# Board.net
KiCad netlist of a schematic drawn in EAGLE
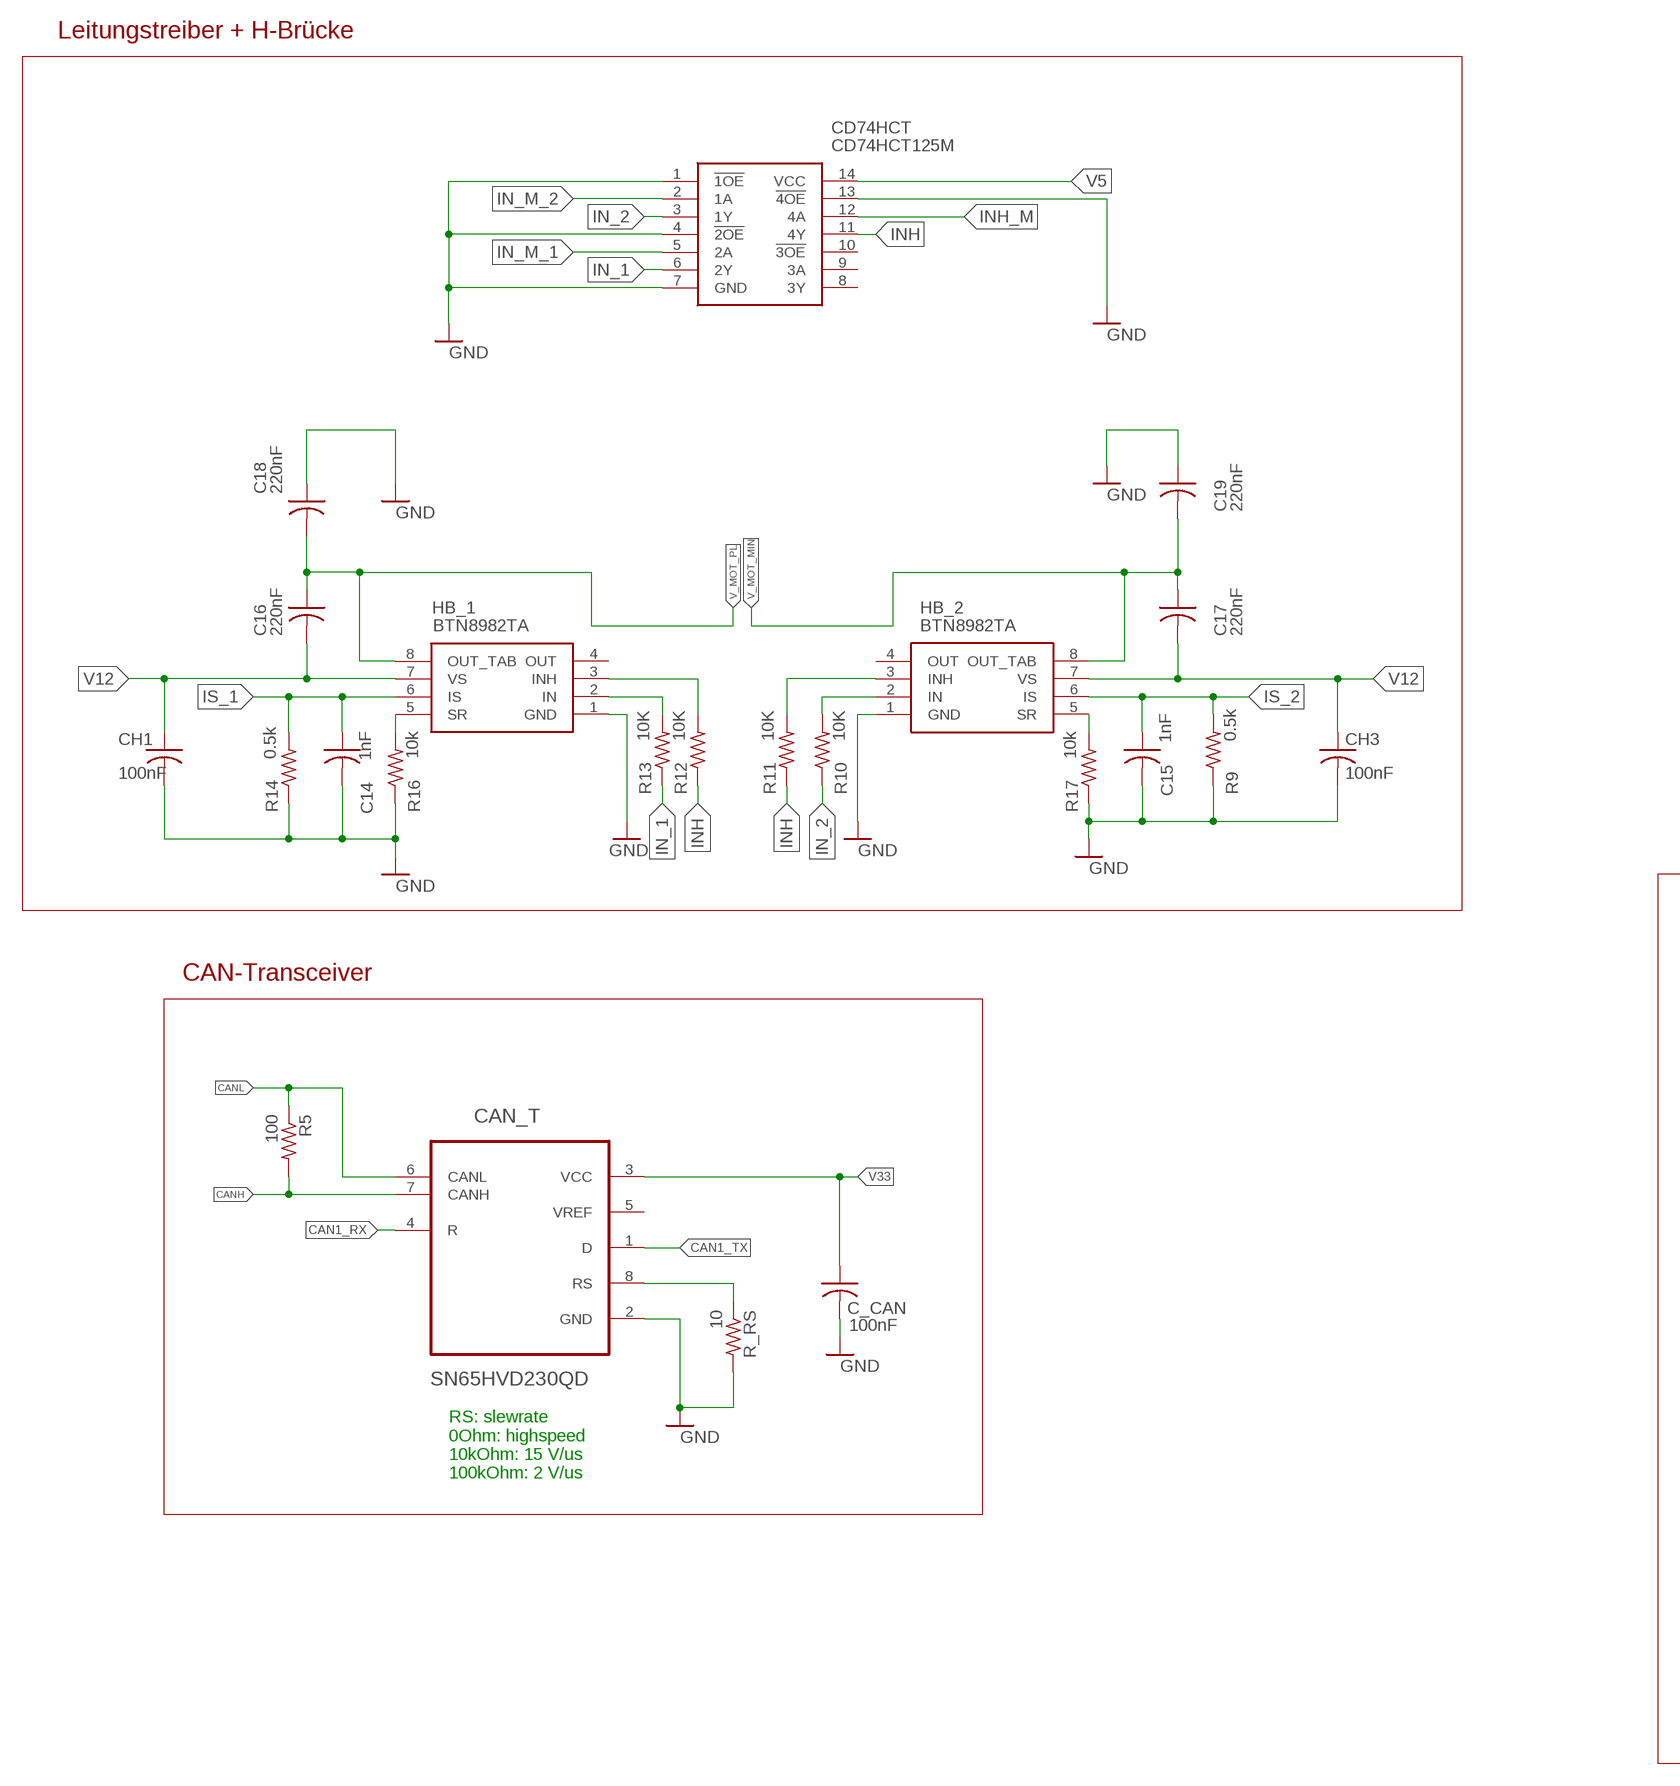
[diagram p0: schematic, sheet 1, part 1 of 2]
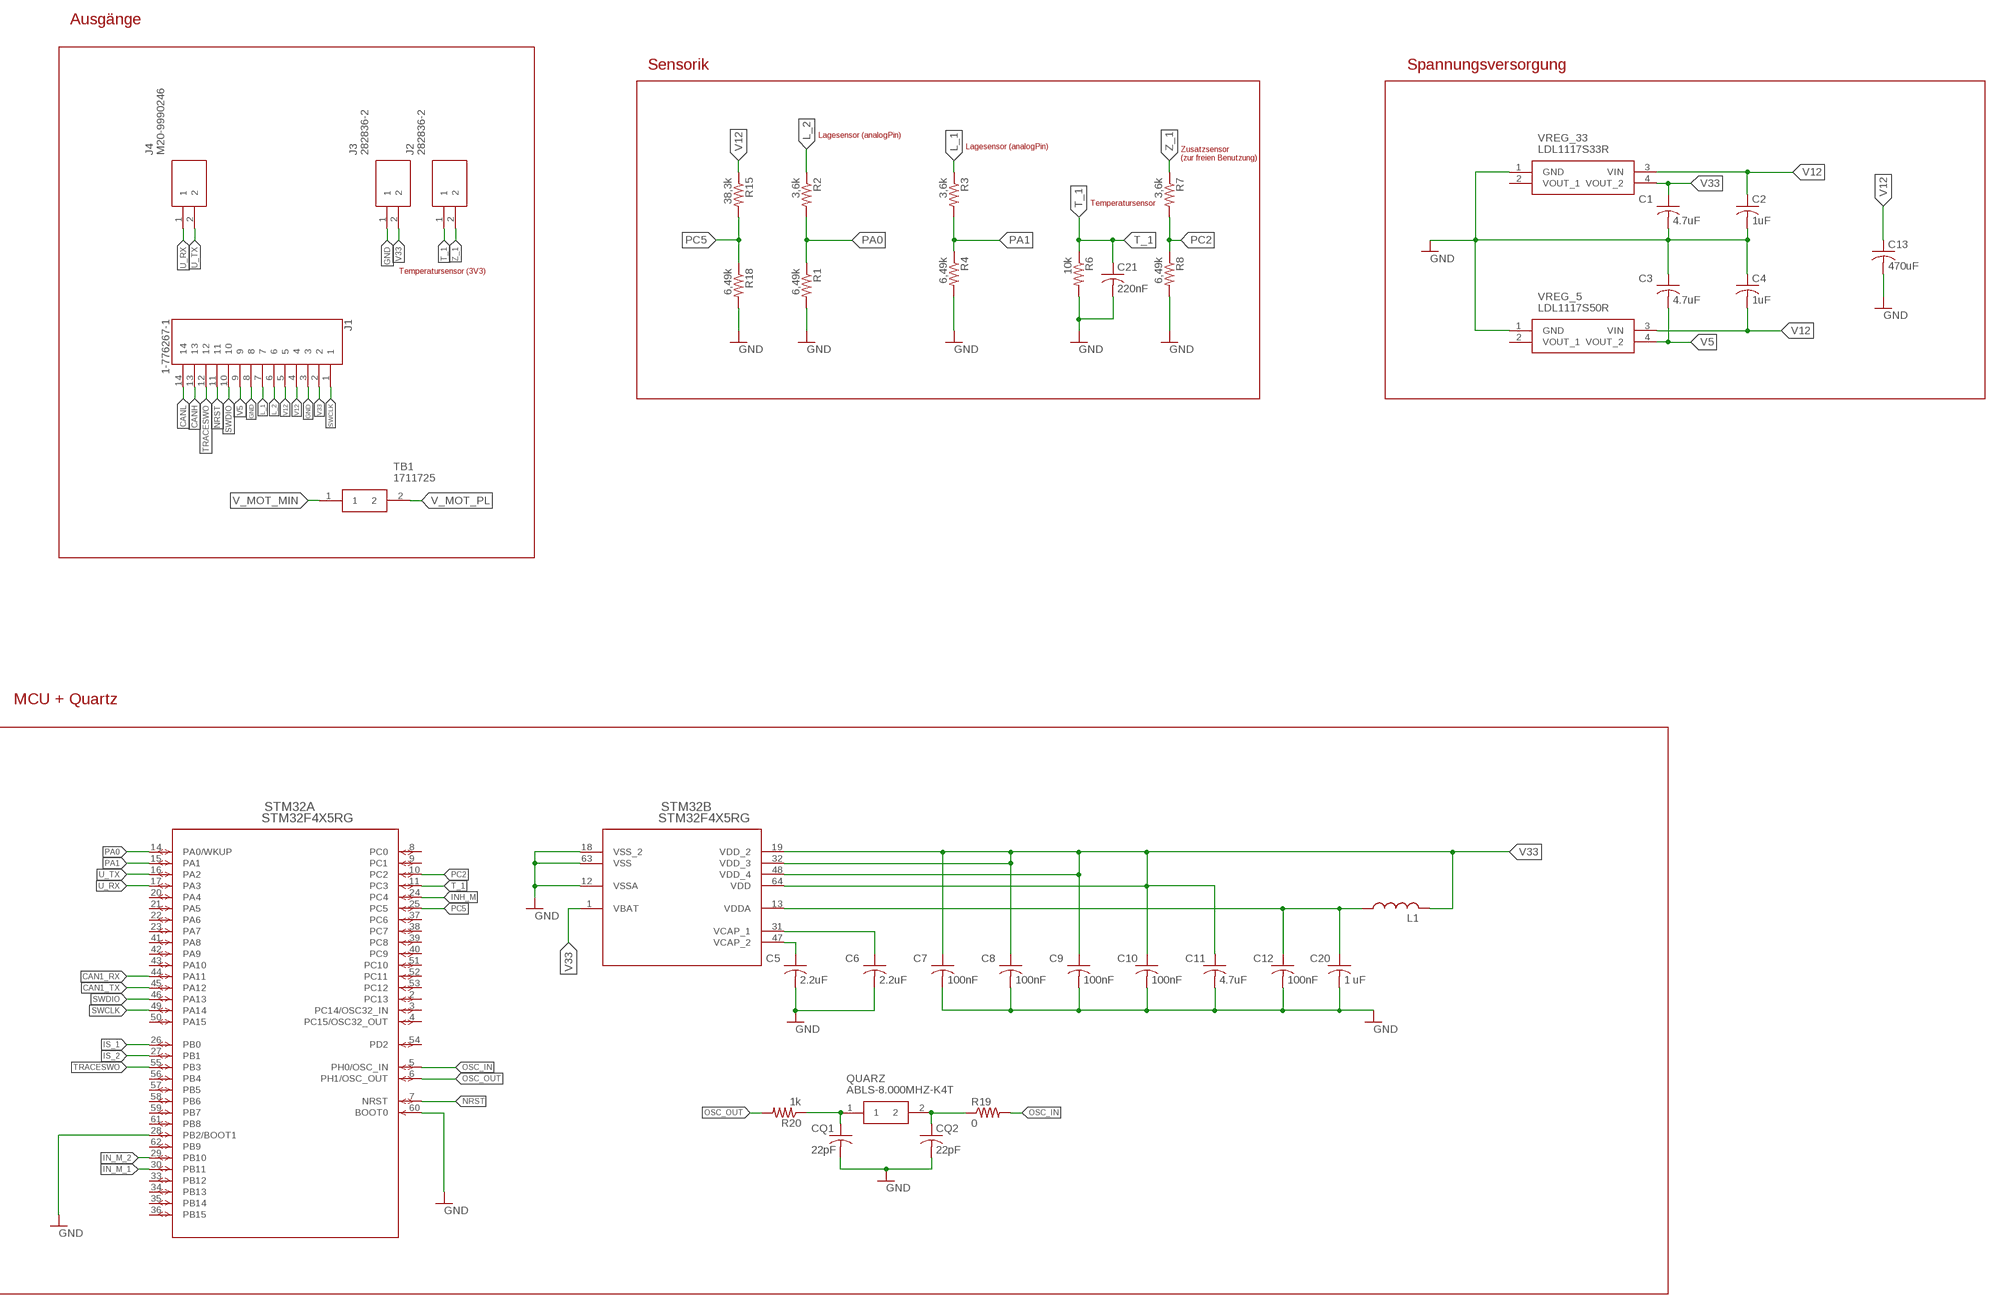
[diagram p1: schematic, sheet 1, part 2 of 2]

(export (version "E")
  (design (tool "Eeschema 10.0.6"))
  (components
    (comp (ref "C1")
      (value "4.7uF")
      (footprint "eagle-import:C1206")
      (libsource (lib "eagle-import") (part "C-USC1206"))
    )
    (comp (ref "C2")
      (value "1uF")
      (footprint "eagle-import:C1206")
      (libsource (lib "eagle-import") (part "C-USC1206"))
    )
    (comp (ref "C3")
      (value "4.7uF")
      (footprint "eagle-import:C1206")
      (libsource (lib "eagle-import") (part "C-USC1206"))
    )
    (comp (ref "C4")
      (value "1uF")
      (footprint "eagle-import:C1206")
      (libsource (lib "eagle-import") (part "C-USC1206"))
    )
    (comp (ref "C5")
      (value "2.2uF")
      (footprint "eagle-import:C1206")
      (libsource (lib "eagle-import") (part "C-USC1206"))
    )
    (comp (ref "C6")
      (value "2.2uF")
      (footprint "eagle-import:C1206")
      (libsource (lib "eagle-import") (part "C-USC1206"))
    )
    (comp (ref "C7")
      (value "100nF")
      (footprint "eagle-import:C1206")
      (libsource (lib "eagle-import") (part "C-USC1206"))
    )
    (comp (ref "C8")
      (value "100nF")
      (footprint "eagle-import:C1206")
      (libsource (lib "eagle-import") (part "C-USC1206"))
    )
    (comp (ref "C9")
      (value "100nF")
      (footprint "eagle-import:C1206")
      (libsource (lib "eagle-import") (part "C-USC1206"))
    )
    (comp (ref "C10")
      (value "100nF")
      (footprint "eagle-import:C1206")
      (libsource (lib "eagle-import") (part "C-USC1206"))
    )
    (comp (ref "C11")
      (value "4.7uF")
      (footprint "eagle-import:C1206")
      (libsource (lib "eagle-import") (part "C-USC1206"))
    )
    (comp (ref "C12")
      (value "100nF")
      (footprint "eagle-import:C1206")
      (libsource (lib "eagle-import") (part "C-USC1206"))
    )
    (comp (ref "C13")
      (value "470uF")
      (footprint "eagle-import:C050-075X075")
      (libsource (lib "eagle-import") (part "C-US050-075X075"))
    )
    (comp (ref "C14")
      (value "1nF")
      (footprint "eagle-import:C1206")
      (libsource (lib "eagle-import") (part "C-USC1206"))
    )
    (comp (ref "C15")
      (value "1nF")
      (footprint "eagle-import:C1206")
      (libsource (lib "eagle-import") (part "C-USC1206"))
    )
    (comp (ref "C16")
      (value "220nF")
      (footprint "eagle-import:C1206")
      (libsource (lib "eagle-import") (part "C-USC1206"))
    )
    (comp (ref "C17")
      (value "220nF")
      (footprint "eagle-import:C1206")
      (libsource (lib "eagle-import") (part "C-USC1206"))
    )
    (comp (ref "C18")
      (value "220nF")
      (footprint "eagle-import:C1206")
      (libsource (lib "eagle-import") (part "C-USC1206"))
    )
    (comp (ref "C19")
      (value "220nF")
      (footprint "eagle-import:C1206")
      (libsource (lib "eagle-import") (part "C-USC1206"))
    )
    (comp (ref "C20")
      (value "1 uF")
      (footprint "eagle-import:C1206")
      (libsource (lib "eagle-import") (part "C-USC1206"))
    )
    (comp (ref "C21")
      (value "220nF")
      (footprint "eagle-import:C1206")
      (libsource (lib "eagle-import") (part "C-USC1206"))
    )
    (comp (ref "CAN_T")
      (value "SN65HVD230QD")
      (footprint "eagle-import:SOIC127P600X175-8N")
      (fields (field (name "MF") "TEXAS INSTRUMENTS") (field (name "MPN") "SN65HVD230QD.."))
      (libsource (lib "eagle-import") (part "SN65HVD230QD"))
    )
    (comp (ref "CD74HCT")
      (value "CD74HCT125M")
      (footprint "eagle-import:SOIC127P600X175-14N")
      (fields (field (name "MOUSER_PART_NUMBER") "595-CD74HCT125M"))
      (libsource (lib "eagle-import") (part "CD74HCT125M"))
    )
    (comp (ref "CH1")
      (value "100nF")
      (footprint "eagle-import:C1206")
      (libsource (lib "eagle-import") (part "C-USC1206"))
    )
    (comp (ref "CH3")
      (value "100nF")
      (footprint "eagle-import:C1206")
      (libsource (lib "eagle-import") (part "C-USC1206"))
    )
    (comp (ref "CQ1")
      (value "22pF")
      (footprint "eagle-import:C0805")
      (libsource (lib "eagle-import") (part "C-USC0805"))
    )
    (comp (ref "CQ2")
      (value "22pF")
      (footprint "eagle-import:C0805")
      (libsource (lib "eagle-import") (part "C-USC0805"))
    )
    (comp (ref "C_CAN")
      (value "100nF")
      (footprint "eagle-import:C1206")
      (libsource (lib "eagle-import") (part "C-USC1206"))
    )
    (comp (ref "HB_1")
      (value "BTN8982TA")
      (footprint "eagle-import:TO127P1500X440-8N")
      (fields (field (name "MOUSER_PART_NUMBER") "726-BTN8982TA"))
      (libsource (lib "eagle-import") (part "BTN8982TA"))
    )
    (comp (ref "HB_2")
      (value "BTN8982TA")
      (footprint "eagle-import:TO127P1500X440-8N")
      (fields (field (name "MOUSER_PART_NUMBER") "726-BTN8982TA"))
      (libsource (lib "eagle-import") (part "BTN8982TA"))
    )
    (comp (ref "J1")
      (value "1-776267-1")
      (footprint "eagle-import:TE_1-776267-1")
      (fields (field (name "DIGI-KEY_PART_NUMBER") "A142413-ND") (field (name "MF") "TE Connectivity"))
      (libsource (lib "eagle-import") (part "1-776267-1"))
    )
    (comp (ref "J2")
      (value "282836-2")
      (footprint "eagle-import:SHDR2W100P0X500_1X2_1000X820X1")
      (fields (field (name "MOUSER_PART_NUMBER") "571-2828362"))
      (libsource (lib "eagle-import") (part "282836-2"))
    )
    (comp (ref "J3")
      (value "282836-2")
      (footprint "eagle-import:SHDR2W100P0X500_1X2_1000X820X1")
      (fields (field (name "MOUSER_PART_NUMBER") "571-2828362"))
      (libsource (lib "eagle-import") (part "282836-2"))
    )
    (comp (ref "J4")
      (value "M20-9990246")
      (footprint "eagle-import:HDRV2W64P0X254_1X2_508X254X864")
      (fields (field (name "MOUSER_PART_NUMBER") "855-M20-9990246"))
      (libsource (lib "eagle-import") (part "M20-9990246"))
    )
    (comp (ref "L1")
      (value "INDUCTOR_0805_N")
      (footprint "eagle-import:RESC0805_N")
      (libsource (lib "eagle-import") (part "INDUCTOR_0805_N"))
    )
    (comp (ref "QUARZ")
      (value "ABLS-8.000MHZ-K4T")
      (footprint "eagle-import:ABLS-12.000MHZ-B2")
      (fields (field (name "MOUSER_PART_NUMBER") "815-ABLS-8.0MK4-T") (field (name "MF") "ABRACON"))
      (libsource (lib "eagle-import") (part "ABLS-8.000MHZ-K4T"))
    )
    (comp (ref "R1")
      (value "6,49k")
      (footprint "eagle-import:R1206")
      (libsource (lib "eagle-import") (part "R-US_R1206"))
    )
    (comp (ref "R2")
      (value "3,6k")
      (footprint "eagle-import:R1206")
      (libsource (lib "eagle-import") (part "R-US_R1206"))
    )
    (comp (ref "R3")
      (value "3,6k")
      (footprint "eagle-import:R1206")
      (libsource (lib "eagle-import") (part "R-US_R1206"))
    )
    (comp (ref "R4")
      (value "6,49k")
      (footprint "eagle-import:R1206")
      (libsource (lib "eagle-import") (part "R-US_R1206"))
    )
    (comp (ref "R5")
      (value "100")
      (footprint "eagle-import:R1206")
      (libsource (lib "eagle-import") (part "R-US_R1206"))
    )
    (comp (ref "R6")
      (value "10k")
      (footprint "eagle-import:R1206")
      (libsource (lib "eagle-import") (part "R-US_R1206"))
    )
    (comp (ref "R7")
      (value "3,6k")
      (footprint "eagle-import:R1206")
      (libsource (lib "eagle-import") (part "R-US_R1206"))
    )
    (comp (ref "R8")
      (value "6,49k")
      (footprint "eagle-import:R1206")
      (libsource (lib "eagle-import") (part "R-US_R1206"))
    )
    (comp (ref "R9")
      (value "0.5k")
      (footprint "eagle-import:R1206")
      (libsource (lib "eagle-import") (part "R-US_R1206"))
    )
    (comp (ref "R10")
      (value "10K")
      (footprint "eagle-import:R1206")
      (libsource (lib "eagle-import") (part "R-US_R1206"))
    )
    (comp (ref "R11")
      (value "10K")
      (footprint "eagle-import:R1206")
      (libsource (lib "eagle-import") (part "R-US_R1206"))
    )
    (comp (ref "R12")
      (value "10K")
      (footprint "eagle-import:R1206")
      (libsource (lib "eagle-import") (part "R-US_R1206"))
    )
    (comp (ref "R13")
      (value "10K")
      (footprint "eagle-import:R1206")
      (libsource (lib "eagle-import") (part "R-US_R1206"))
    )
    (comp (ref "R14")
      (value "0.5k")
      (footprint "eagle-import:R1206")
      (libsource (lib "eagle-import") (part "R-US_R1206"))
    )
    (comp (ref "R15")
      (value "38,3k")
      (footprint "eagle-import:R1206")
      (libsource (lib "eagle-import") (part "R-US_R1206"))
    )
    (comp (ref "R16")
      (value "10k")
      (footprint "eagle-import:R0805")
      (libsource (lib "eagle-import") (part "resistor_348_R-US_R0805"))
    )
    (comp (ref "R17")
      (value "10k")
      (footprint "eagle-import:R0805")
      (libsource (lib "eagle-import") (part "resistor_348_R-US_R0805"))
    )
    (comp (ref "R18")
      (value "6,49k")
      (footprint "eagle-import:R1206")
      (libsource (lib "eagle-import") (part "R-US_R1206"))
    )
    (comp (ref "R19")
      (value "0")
      (footprint "eagle-import:R0805")
      (libsource (lib "eagle-import") (part "resistor_348_R-US_R0805"))
    )
    (comp (ref "R20")
      (value "1k")
      (footprint "eagle-import:R0805")
      (libsource (lib "eagle-import") (part "resistor_348_R-US_R0805"))
    )
    (comp (ref "R_RS")
      (value "10")
      (footprint "eagle-import:R1206")
      (libsource (lib "eagle-import") (part "R-US_R1206"))
    )
    (comp (ref "STM32")
      (value "STM32F4X5RG")
      (footprint "eagle-import:LQFP64-10X10MM")
      (fields (field (name "OC_FARNELL") "unknown"))
      (libsource (lib "eagle-import") (part "STM32F4X5RG"))
    )
    (comp (ref "TB1")
      (value "1711725")
      (footprint "eagle-import:PHEONIX-5.08PITCH-2PIN")
      (fields (field (name "MOUSER_PART_NUMBER") "651-1711725"))
      (libsource (lib "eagle-import") (part "1711725"))
    )
    (comp (ref "VREG_5")
      (value "LDL1117S50R")
      (footprint "eagle-import:SOT230P700X180-4N")
      (fields (field (name "MOUSER_PART_NUMBER") "511-LDL1117S50R") (field (name "MF") "STMICROELECTRONICS"))
      (libsource (lib "eagle-import") (part "LDL1117S50R"))
    )
    (comp (ref "VREG_33")
      (value "LDL1117S33R")
      (footprint "eagle-import:SOT230P700X180-4N")
      (fields (field (name "MOUSER_PART_NUMBER") "511-LDL1117S33R") (field (name "MF") "STMICROELECTRONICS"))
      (libsource (lib "eagle-import") (part "LDL1117S33R"))
    )
  )
  (nets
    (net (code "1") (name "CAN1_RX") (class "Default")
      (node (ref "CAN_T") (pin "4") (pinfunction "R_4") (pintype "output"))
      (node (ref "STM32") (pin "44") (pinfunction "PA11_44") (pintype "bidirectional"))
    )
    (net (code "2") (name "CAN1_TX") (class "Default")
      (node (ref "CAN_T") (pin "1") (pinfunction "D_1") (pintype "input"))
      (node (ref "STM32") (pin "45") (pinfunction "PA12_45") (pintype "bidirectional"))
    )
    (net (code "3") (name "CANH") (class "Default")
      (node (ref "CAN_T") (pin "7") (pinfunction "CANH_7") (pintype "output"))
      (node (ref "J1") (pin "13") (pinfunction "13_13") (pintype "passive"))
      (node (ref "R5") (pin "2") (pinfunction "2_2") (pintype "passive"))
    )
    (net (code "4") (name "CANL") (class "Default")
      (node (ref "CAN_T") (pin "6") (pinfunction "CANL_6") (pintype "output"))
      (node (ref "J1") (pin "14") (pinfunction "14_14") (pintype "passive"))
      (node (ref "R5") (pin "1") (pinfunction "1_1") (pintype "passive"))
    )
    (net (code "5") (name "GND") (class "Default")
      (node (ref "C1") (pin "2") (pinfunction "2_2") (pintype "passive"))
      (node (ref "C10") (pin "2") (pinfunction "2_2") (pintype "passive"))
      (node (ref "C11") (pin "2") (pinfunction "2_2") (pintype "passive"))
      (node (ref "C12") (pin "2") (pinfunction "2_2") (pintype "passive"))
      (node (ref "C13") (pin "2") (pinfunction "2_2") (pintype "passive"))
      (node (ref "C14") (pin "2") (pinfunction "2_2") (pintype "passive"))
      (node (ref "C15") (pin "2") (pinfunction "2_2") (pintype "passive"))
      (node (ref "C18") (pin "1") (pinfunction "1_1") (pintype "passive"))
      (node (ref "C19") (pin "1") (pinfunction "1_1") (pintype "passive"))
      (node (ref "C2") (pin "2") (pinfunction "2_2") (pintype "passive"))
      (node (ref "C20") (pin "2") (pinfunction "2_2") (pintype "passive"))
      (node (ref "C21") (pin "2") (pinfunction "2_2") (pintype "passive"))
      (node (ref "C3") (pin "1") (pinfunction "1_1") (pintype "passive"))
      (node (ref "C4") (pin "1") (pinfunction "1_1") (pintype "passive"))
      (node (ref "C5") (pin "2") (pinfunction "2_2") (pintype "passive"))
      (node (ref "C6") (pin "2") (pinfunction "2_2") (pintype "passive"))
      (node (ref "C7") (pin "2") (pinfunction "2_2") (pintype "passive"))
      (node (ref "C8") (pin "2") (pinfunction "2_2") (pintype "passive"))
      (node (ref "C9") (pin "2") (pinfunction "2_2") (pintype "passive"))
      (node (ref "CAN_T") (pin "2") (pinfunction "GND_2") (pintype "passive"))
      (node (ref "CD74HCT") (pin "1") (pinfunction "~{1OE}_1") (pintype "bidirectional"))
      (node (ref "CD74HCT") (pin "13") (pinfunction "~{4OE}_13") (pintype "bidirectional"))
      (node (ref "CD74HCT") (pin "4") (pinfunction "~{2OE}_4") (pintype "bidirectional"))
      (node (ref "CD74HCT") (pin "7") (pinfunction "GND_7") (pintype "power_in"))
      (node (ref "CH1") (pin "2") (pinfunction "2_2") (pintype "passive"))
      (node (ref "CH3") (pin "2") (pinfunction "2_2") (pintype "passive"))
      (node (ref "CQ1") (pin "2") (pinfunction "2_2") (pintype "passive"))
      (node (ref "CQ2") (pin "2") (pinfunction "2_2") (pintype "passive"))
      (node (ref "C_CAN") (pin "2") (pinfunction "2_2") (pintype "passive"))
      (node (ref "HB_1") (pin "1") (pinfunction "GND_1") (pintype "power_in"))
      (node (ref "HB_2") (pin "1") (pinfunction "GND_1") (pintype "power_in"))
      (node (ref "J1") (pin "3") (pinfunction "3_3") (pintype "passive"))
      (node (ref "J1") (pin "8") (pinfunction "8_8") (pintype "passive"))
      (node (ref "J3") (pin "1") (pinfunction "1_1") (pintype "bidirectional"))
      (node (ref "R1") (pin "2") (pinfunction "2_2") (pintype "passive"))
      (node (ref "R14") (pin "1") (pinfunction "1_1") (pintype "passive"))
      (node (ref "R16") (pin "1") (pinfunction "1_1") (pintype "passive"))
      (node (ref "R17") (pin "1") (pinfunction "1_1") (pintype "passive"))
      (node (ref "R18") (pin "2") (pinfunction "2_2") (pintype "passive"))
      (node (ref "R4") (pin "2") (pinfunction "2_2") (pintype "passive"))
      (node (ref "R6") (pin "2") (pinfunction "2_2") (pintype "passive"))
      (node (ref "R8") (pin "2") (pinfunction "2_2") (pintype "passive"))
      (node (ref "R9") (pin "1") (pinfunction "1_1") (pintype "passive"))
      (node (ref "R_RS") (pin "2") (pinfunction "2_2") (pintype "passive"))
      (node (ref "STM32") (pin "12") (pinfunction "VSSA_12") (pintype "power_in"))
      (node (ref "STM32") (pin "18") (pinfunction "VSS_2_18") (pintype "power_in"))
      (node (ref "STM32") (pin "28") (pinfunction "PB2/BOOT1_28") (pintype "bidirectional"))
      (node (ref "STM32") (pin "60") (pinfunction "BOOT0_60") (pintype "input"))
      (node (ref "STM32") (pin "63") (pinfunction "VSS_63") (pintype "power_in"))
      (node (ref "VREG_33") (pin "1") (pinfunction "GND_1") (pintype "power_in"))
      (node (ref "VREG_5") (pin "1") (pinfunction "GND_1") (pintype "bidirectional"))
    )
    (net (code "6") (name "INH") (class "Default")
      (node (ref "CD74HCT") (pin "11") (pinfunction "4Y_11") (pintype "bidirectional"))
      (node (ref "R11") (pin "1") (pinfunction "1_1") (pintype "passive"))
      (node (ref "R12") (pin "1") (pinfunction "1_1") (pintype "passive"))
    )
    (net (code "7") (name "INH_M") (class "Default")
      (node (ref "CD74HCT") (pin "12") (pinfunction "4A_12") (pintype "bidirectional"))
      (node (ref "STM32") (pin "24") (pinfunction "PC4_24") (pintype "bidirectional"))
    )
    (net (code "8") (name "IN_1") (class "Default")
      (node (ref "CD74HCT") (pin "6") (pinfunction "2Y_6") (pintype "bidirectional"))
      (node (ref "R13") (pin "1") (pinfunction "1_1") (pintype "passive"))
    )
    (net (code "9") (name "IN_2") (class "Default")
      (node (ref "CD74HCT") (pin "3") (pinfunction "1Y_3") (pintype "bidirectional"))
      (node (ref "R10") (pin "1") (pinfunction "1_1") (pintype "passive"))
    )
    (net (code "10") (name "IN_M_1") (class "Default")
      (node (ref "CD74HCT") (pin "5") (pinfunction "2A_5") (pintype "bidirectional"))
      (node (ref "STM32") (pin "30") (pinfunction "PB11_30") (pintype "bidirectional"))
    )
    (net (code "11") (name "IN_M_2") (class "Default")
      (node (ref "CD74HCT") (pin "2") (pinfunction "1A_2") (pintype "bidirectional"))
      (node (ref "STM32") (pin "29") (pinfunction "PB10_29") (pintype "bidirectional"))
    )
    (net (code "12") (name "IS_1") (class "Default")
      (node (ref "C14") (pin "1") (pinfunction "1_1") (pintype "passive"))
      (node (ref "HB_1") (pin "6") (pinfunction "IS_6") (pintype "bidirectional"))
      (node (ref "R14") (pin "2") (pinfunction "2_2") (pintype "passive"))
      (node (ref "STM32") (pin "26") (pinfunction "PB0_26") (pintype "bidirectional"))
    )
    (net (code "13") (name "IS_2") (class "Default")
      (node (ref "C15") (pin "1") (pinfunction "1_1") (pintype "passive"))
      (node (ref "HB_2") (pin "6") (pinfunction "IS_6") (pintype "bidirectional"))
      (node (ref "R9") (pin "2") (pinfunction "2_2") (pintype "passive"))
      (node (ref "STM32") (pin "27") (pinfunction "PB1_27") (pintype "bidirectional"))
    )
    (net (code "14") (name "L_1") (class "Default")
      (node (ref "J1") (pin "7") (pinfunction "7_7") (pintype "passive"))
      (node (ref "R3") (pin "1") (pinfunction "1_1") (pintype "passive"))
    )
    (net (code "15") (name "L_2") (class "Default")
      (node (ref "J1") (pin "6") (pinfunction "6_6") (pintype "passive"))
      (node (ref "R2") (pin "1") (pinfunction "1_1") (pintype "passive"))
    )
    (net (code "16") (name "NRST") (class "Default")
      (node (ref "J1") (pin "11") (pinfunction "11_11") (pintype "passive"))
      (node (ref "STM32") (pin "7") (pinfunction "NRST_7") (pintype "bidirectional"))
    )
    (net (code "17") (name "Net-(CAN_T-RS)") (class "Default")
      (node (ref "CAN_T") (pin "8") (pinfunction "RS_8") (pintype "input"))
      (node (ref "R_RS") (pin "1") (pinfunction "1_1") (pintype "passive"))
    )
    (net (code "18") (name "Net-(CQ1-Pad1)") (class "Default")
      (node (ref "CQ1") (pin "1") (pinfunction "1_1") (pintype "passive"))
      (node (ref "QUARZ") (pin "1") (pinfunction "1_1") (pintype "bidirectional"))
      (node (ref "R20") (pin "1") (pinfunction "1_1") (pintype "passive"))
    )
    (net (code "19") (name "Net-(CQ2-Pad1)") (class "Default")
      (node (ref "CQ2") (pin "1") (pinfunction "1_1") (pintype "passive"))
      (node (ref "QUARZ") (pin "2") (pinfunction "2_2") (pintype "bidirectional"))
      (node (ref "R19") (pin "1") (pinfunction "1_1") (pintype "passive"))
    )
    (net (code "20") (name "Net-(HB_1-IN)") (class "Default")
      (node (ref "HB_1") (pin "2") (pinfunction "IN_2") (pintype "input"))
      (node (ref "R13") (pin "2") (pinfunction "2_2") (pintype "passive"))
    )
    (net (code "21") (name "Net-(HB_1-INH)") (class "Default")
      (node (ref "HB_1") (pin "3") (pinfunction "INH_3") (pintype "input"))
      (node (ref "R12") (pin "2") (pinfunction "2_2") (pintype "passive"))
    )
    (net (code "22") (name "Net-(HB_1-SR)") (class "Default")
      (node (ref "HB_1") (pin "5") (pinfunction "SR_5") (pintype "bidirectional"))
      (node (ref "R16") (pin "2") (pinfunction "2_2") (pintype "passive"))
    )
    (net (code "23") (name "Net-(HB_2-IN)") (class "Default")
      (node (ref "HB_2") (pin "2") (pinfunction "IN_2") (pintype "input"))
      (node (ref "R10") (pin "2") (pinfunction "2_2") (pintype "passive"))
    )
    (net (code "24") (name "Net-(HB_2-INH)") (class "Default")
      (node (ref "HB_2") (pin "3") (pinfunction "INH_3") (pintype "input"))
      (node (ref "R11") (pin "2") (pinfunction "2_2") (pintype "passive"))
    )
    (net (code "25") (name "Net-(HB_2-SR)") (class "Default")
      (node (ref "HB_2") (pin "5") (pinfunction "SR_5") (pintype "bidirectional"))
      (node (ref "R17") (pin "2") (pinfunction "2_2") (pintype "passive"))
    )
    (net (code "26") (name "Net-(STM32B-VCAP_1)") (class "Default")
      (node (ref "C6") (pin "1") (pinfunction "1_1") (pintype "passive"))
      (node (ref "STM32") (pin "31") (pinfunction "VCAP_1_31") (pintype "power_in"))
    )
    (net (code "27") (name "Net-(STM32B-VCAP_2)") (class "Default")
      (node (ref "C5") (pin "1") (pinfunction "1_1") (pintype "passive"))
      (node (ref "STM32") (pin "47") (pinfunction "VCAP_2_47") (pintype "power_in"))
    )
    (net (code "28") (name "Net-(STM32B-VDDA)") (class "Default")
      (node (ref "C12") (pin "1") (pinfunction "1_1") (pintype "passive"))
      (node (ref "C20") (pin "1") (pinfunction "1_1") (pintype "passive"))
      (node (ref "L1") (pin "1") (pinfunction "1_1") (pintype "passive"))
      (node (ref "STM32") (pin "13") (pinfunction "VDDA_13") (pintype "power_in"))
    )
    (net (code "29") (name "OSC_IN") (class "Default")
      (node (ref "R19") (pin "2") (pinfunction "2_2") (pintype "passive"))
      (node (ref "STM32") (pin "5") (pinfunction "PH0/OSC_IN_5") (pintype "bidirectional"))
    )
    (net (code "30") (name "OSC_OUT") (class "Default")
      (node (ref "R20") (pin "2") (pinfunction "2_2") (pintype "passive"))
      (node (ref "STM32") (pin "6") (pinfunction "PH1/OSC_OUT_6") (pintype "bidirectional"))
    )
    (net (code "31") (name "PA0") (class "Default")
      (node (ref "R1") (pin "1") (pinfunction "1_1") (pintype "passive"))
      (node (ref "R2") (pin "2") (pinfunction "2_2") (pintype "passive"))
      (node (ref "STM32") (pin "14") (pinfunction "PA0/WKUP_14") (pintype "bidirectional"))
    )
    (net (code "32") (name "PA1") (class "Default")
      (node (ref "R3") (pin "2") (pinfunction "2_2") (pintype "passive"))
      (node (ref "R4") (pin "1") (pinfunction "1_1") (pintype "passive"))
      (node (ref "STM32") (pin "15") (pinfunction "PA1_15") (pintype "bidirectional"))
    )
    (net (code "33") (name "PC2") (class "Default")
      (node (ref "R7") (pin "2") (pinfunction "2_2") (pintype "passive"))
      (node (ref "R8") (pin "1") (pinfunction "1_1") (pintype "passive"))
      (node (ref "STM32") (pin "10") (pinfunction "PC2_10") (pintype "bidirectional"))
    )
    (net (code "34") (name "PC5") (class "Default")
      (node (ref "R15") (pin "2") (pinfunction "2_2") (pintype "passive"))
      (node (ref "R18") (pin "1") (pinfunction "1_1") (pintype "passive"))
      (node (ref "STM32") (pin "25") (pinfunction "PC5_25") (pintype "bidirectional"))
    )
    (net (code "35") (name "SWCLK") (class "Default")
      (node (ref "J1") (pin "1") (pinfunction "1_1") (pintype "passive"))
      (node (ref "STM32") (pin "49") (pinfunction "PA14_49") (pintype "bidirectional"))
    )
    (net (code "36") (name "SWDIO") (class "Default")
      (node (ref "J1") (pin "10") (pinfunction "10_10") (pintype "passive"))
      (node (ref "STM32") (pin "46") (pinfunction "PA13_46") (pintype "bidirectional"))
    )
    (net (code "37") (name "TRACESWO") (class "Default")
      (node (ref "J1") (pin "12") (pinfunction "12_12") (pintype "passive"))
      (node (ref "STM32") (pin "55") (pinfunction "PB3_55") (pintype "bidirectional"))
    )
    (net (code "38") (name "T_1") (class "Default")
      (node (ref "C21") (pin "1") (pinfunction "1_1") (pintype "passive"))
      (node (ref "J2") (pin "1") (pinfunction "1_1") (pintype "bidirectional"))
      (node (ref "R6") (pin "1") (pinfunction "1_1") (pintype "passive"))
      (node (ref "STM32") (pin "11") (pinfunction "PC3_11") (pintype "bidirectional"))
    )
    (net (code "39") (name "U_RX") (class "Default")
      (node (ref "J4") (pin "1") (pinfunction "1_1") (pintype "bidirectional"))
      (node (ref "STM32") (pin "17") (pinfunction "PA3_17") (pintype "bidirectional"))
    )
    (net (code "40") (name "U_TX") (class "Default")
      (node (ref "J4") (pin "2") (pinfunction "2_2") (pintype "bidirectional"))
      (node (ref "STM32") (pin "16") (pinfunction "PA2_16") (pintype "bidirectional"))
    )
    (net (code "41") (name "V5") (class "Default")
      (node (ref "C3") (pin "2") (pinfunction "2_2") (pintype "passive"))
      (node (ref "CD74HCT") (pin "14") (pinfunction "VCC_14") (pintype "power_in"))
      (node (ref "J1") (pin "9") (pinfunction "9_9") (pintype "passive"))
      (node (ref "VREG_5") (pin "4") (pinfunction "VOUT_2_4") (pintype "bidirectional"))
    )
    (net (code "42") (name "V12") (class "Default")
      (node (ref "C13") (pin "1") (pinfunction "1_1") (pintype "passive"))
      (node (ref "C16") (pin "2") (pinfunction "2_2") (pintype "passive"))
      (node (ref "C17") (pin "2") (pinfunction "2_2") (pintype "passive"))
      (node (ref "C2") (pin "1") (pinfunction "1_1") (pintype "passive"))
      (node (ref "C4") (pin "2") (pinfunction "2_2") (pintype "passive"))
      (node (ref "CH1") (pin "1") (pinfunction "1_1") (pintype "passive"))
      (node (ref "CH3") (pin "1") (pinfunction "1_1") (pintype "passive"))
      (node (ref "HB_1") (pin "7") (pinfunction "VS_7") (pintype "bidirectional"))
      (node (ref "HB_2") (pin "7") (pinfunction "VS_7") (pintype "bidirectional"))
      (node (ref "J1") (pin "4") (pinfunction "4_4") (pintype "passive"))
      (node (ref "J1") (pin "5") (pinfunction "5_5") (pintype "passive"))
      (node (ref "R15") (pin "1") (pinfunction "1_1") (pintype "passive"))
      (node (ref "VREG_33") (pin "3") (pinfunction "VIN_3") (pintype "input"))
      (node (ref "VREG_5") (pin "3") (pinfunction "VIN_3") (pintype "bidirectional"))
    )
    (net (code "43") (name "V33") (class "Default")
      (node (ref "C1") (pin "1") (pinfunction "1_1") (pintype "passive"))
      (node (ref "C10") (pin "1") (pinfunction "1_1") (pintype "passive"))
      (node (ref "C11") (pin "1") (pinfunction "1_1") (pintype "passive"))
      (node (ref "C7") (pin "1") (pinfunction "1_1") (pintype "passive"))
      (node (ref "C8") (pin "1") (pinfunction "1_1") (pintype "passive"))
      (node (ref "C9") (pin "1") (pinfunction "1_1") (pintype "passive"))
      (node (ref "CAN_T") (pin "3") (pinfunction "VCC_3") (pintype "power_in"))
      (node (ref "C_CAN") (pin "1") (pinfunction "1_1") (pintype "passive"))
      (node (ref "J1") (pin "2") (pinfunction "2_2") (pintype "passive"))
      (node (ref "J3") (pin "2") (pinfunction "2_2") (pintype "bidirectional"))
      (node (ref "L1") (pin "2") (pinfunction "2_2") (pintype "passive"))
      (node (ref "STM32") (pin "1") (pinfunction "VBAT_1") (pintype "power_in"))
      (node (ref "STM32") (pin "19") (pinfunction "VDD_2_19") (pintype "power_in"))
      (node (ref "STM32") (pin "32") (pinfunction "VDD_3_32") (pintype "power_in"))
      (node (ref "STM32") (pin "48") (pinfunction "VDD_4_48") (pintype "power_in"))
      (node (ref "STM32") (pin "64") (pinfunction "VDD_64") (pintype "power_in"))
      (node (ref "VREG_33") (pin "4") (pinfunction "VOUT_2_4") (pintype "output"))
    )
    (net (code "44") (name "V_MOT_MIN") (class "Default")
      (node (ref "C17") (pin "1") (pinfunction "1_1") (pintype "passive"))
      (node (ref "C19") (pin "2") (pinfunction "2_2") (pintype "passive"))
      (node (ref "HB_2") (pin "8") (pinfunction "OUT_TAB_8") (pintype "output"))
      (node (ref "TB1") (pin "1") (pinfunction "1_1") (pintype "bidirectional"))
    )
    (net (code "45") (name "V_MOT_PL") (class "Default")
      (node (ref "C16") (pin "1") (pinfunction "1_1") (pintype "passive"))
      (node (ref "C18") (pin "2") (pinfunction "2_2") (pintype "passive"))
      (node (ref "HB_1") (pin "8") (pinfunction "OUT_TAB_8") (pintype "output"))
      (node (ref "TB1") (pin "2") (pinfunction "2_2") (pintype "bidirectional"))
    )
    (net (code "46") (name "Z_1") (class "Default")
      (node (ref "J2") (pin "2") (pinfunction "2_2") (pintype "bidirectional"))
      (node (ref "R7") (pin "1") (pinfunction "1_1") (pintype "passive"))
    )
    (net (code "47") (name "unconnected-(CAN_T-VREF-Pad5)") (class "Default")
      (node (ref "CAN_T") (pin "5") (pinfunction "VREF_5") (pintype "input"))
    )
    (net (code "48") (name "unconnected-(CD74HCT-3A-Pad9)") (class "Default")
      (node (ref "CD74HCT") (pin "9") (pinfunction "3A_9") (pintype "bidirectional"))
    )
    (net (code "49") (name "unconnected-(CD74HCT-3Y-Pad8)") (class "Default")
      (node (ref "CD74HCT") (pin "8") (pinfunction "3Y_8") (pintype "bidirectional"))
    )
    (net (code "50") (name "unconnected-(CD74HCT-~{3OE}-Pad10)") (class "Default")
      (node (ref "CD74HCT") (pin "10") (pinfunction "~{3OE}_10") (pintype "bidirectional"))
    )
    (net (code "51") (name "unconnected-(HB_1-OUT-Pad4)") (class "Default")
      (node (ref "HB_1") (pin "4") (pinfunction "OUT_4") (pintype "output"))
    )
    (net (code "52") (name "unconnected-(HB_2-OUT-Pad4)") (class "Default")
      (node (ref "HB_2") (pin "4") (pinfunction "OUT_4") (pintype "output"))
    )
    (net (code "53") (name "unconnected-(STM32A-PA4-Pad20)") (class "Default")
      (node (ref "STM32") (pin "20") (pinfunction "PA4_20") (pintype "bidirectional"))
    )
    (net (code "54") (name "unconnected-(STM32A-PA5-Pad21)") (class "Default")
      (node (ref "STM32") (pin "21") (pinfunction "PA5_21") (pintype "bidirectional"))
    )
    (net (code "55") (name "unconnected-(STM32A-PA6-Pad22)") (class "Default")
      (node (ref "STM32") (pin "22") (pinfunction "PA6_22") (pintype "bidirectional"))
    )
    (net (code "56") (name "unconnected-(STM32A-PA7-Pad23)") (class "Default")
      (node (ref "STM32") (pin "23") (pinfunction "PA7_23") (pintype "bidirectional"))
    )
    (net (code "57") (name "unconnected-(STM32A-PA8-Pad41)") (class "Default")
      (node (ref "STM32") (pin "41") (pinfunction "PA8_41") (pintype "bidirectional"))
    )
    (net (code "58") (name "unconnected-(STM32A-PA9-Pad42)") (class "Default")
      (node (ref "STM32") (pin "42") (pinfunction "PA9_42") (pintype "bidirectional"))
    )
    (net (code "59") (name "unconnected-(STM32A-PA10-Pad43)") (class "Default")
      (node (ref "STM32") (pin "43") (pinfunction "PA10_43") (pintype "bidirectional"))
    )
    (net (code "60") (name "unconnected-(STM32A-PA15-Pad50)") (class "Default")
      (node (ref "STM32") (pin "50") (pinfunction "PA15_50") (pintype "bidirectional"))
    )
    (net (code "61") (name "unconnected-(STM32A-PB4-Pad56)") (class "Default")
      (node (ref "STM32") (pin "56") (pinfunction "PB4_56") (pintype "bidirectional"))
    )
    (net (code "62") (name "unconnected-(STM32A-PB5-Pad57)") (class "Default")
      (node (ref "STM32") (pin "57") (pinfunction "PB5_57") (pintype "bidirectional"))
    )
    (net (code "63") (name "unconnected-(STM32A-PB6-Pad58)") (class "Default")
      (node (ref "STM32") (pin "58") (pinfunction "PB6_58") (pintype "bidirectional"))
    )
    (net (code "64") (name "unconnected-(STM32A-PB7-Pad59)") (class "Default")
      (node (ref "STM32") (pin "59") (pinfunction "PB7_59") (pintype "bidirectional"))
    )
    (net (code "65") (name "unconnected-(STM32A-PB8-Pad61)") (class "Default")
      (node (ref "STM32") (pin "61") (pinfunction "PB8_61") (pintype "bidirectional"))
    )
    (net (code "66") (name "unconnected-(STM32A-PB9-Pad62)") (class "Default")
      (node (ref "STM32") (pin "62") (pinfunction "PB9_62") (pintype "bidirectional"))
    )
    (net (code "67") (name "unconnected-(STM32A-PB12-Pad33)") (class "Default")
      (node (ref "STM32") (pin "33") (pinfunction "PB12_33") (pintype "bidirectional"))
    )
    (net (code "68") (name "unconnected-(STM32A-PB13-Pad34)") (class "Default")
      (node (ref "STM32") (pin "34") (pinfunction "PB13_34") (pintype "bidirectional"))
    )
    (net (code "69") (name "unconnected-(STM32A-PB14-Pad35)") (class "Default")
      (node (ref "STM32") (pin "35") (pinfunction "PB14_35") (pintype "bidirectional"))
    )
    (net (code "70") (name "unconnected-(STM32A-PB15-Pad36)") (class "Default")
      (node (ref "STM32") (pin "36") (pinfunction "PB15_36") (pintype "bidirectional"))
    )
    (net (code "71") (name "unconnected-(STM32A-PC0-Pad8)") (class "Default")
      (node (ref "STM32") (pin "8") (pinfunction "PC0_8") (pintype "bidirectional"))
    )
    (net (code "72") (name "unconnected-(STM32A-PC1-Pad9)") (class "Default")
      (node (ref "STM32") (pin "9") (pinfunction "PC1_9") (pintype "bidirectional"))
    )
    (net (code "73") (name "unconnected-(STM32A-PC6-Pad37)") (class "Default")
      (node (ref "STM32") (pin "37") (pinfunction "PC6_37") (pintype "bidirectional"))
    )
    (net (code "74") (name "unconnected-(STM32A-PC7-Pad38)") (class "Default")
      (node (ref "STM32") (pin "38") (pinfunction "PC7_38") (pintype "bidirectional"))
    )
    (net (code "75") (name "unconnected-(STM32A-PC8-Pad39)") (class "Default")
      (node (ref "STM32") (pin "39") (pinfunction "PC8_39") (pintype "bidirectional"))
    )
    (net (code "76") (name "unconnected-(STM32A-PC9-Pad40)") (class "Default")
      (node (ref "STM32") (pin "40") (pinfunction "PC9_40") (pintype "bidirectional"))
    )
    (net (code "77") (name "unconnected-(STM32A-PC10-Pad51)") (class "Default")
      (node (ref "STM32") (pin "51") (pinfunction "PC10_51") (pintype "bidirectional"))
    )
    (net (code "78") (name "unconnected-(STM32A-PC11-Pad52)") (class "Default")
      (node (ref "STM32") (pin "52") (pinfunction "PC11_52") (pintype "bidirectional"))
    )
    (net (code "79") (name "unconnected-(STM32A-PC12-Pad53)") (class "Default")
      (node (ref "STM32") (pin "53") (pinfunction "PC12_53") (pintype "bidirectional"))
    )
    (net (code "80") (name "unconnected-(STM32A-PC13-Pad2)") (class "Default")
      (node (ref "STM32") (pin "2") (pinfunction "PC13_2") (pintype "bidirectional"))
    )
    (net (code "81") (name "unconnected-(STM32A-PC14{slash}OSC32_IN-Pad3)") (class "Default")
      (node (ref "STM32") (pin "3") (pinfunction "PC14/OSC32_IN_3") (pintype "bidirectional"))
    )
    (net (code "82") (name "unconnected-(STM32A-PC15{slash}OSC32_OUT-Pad4)") (class "Default")
      (node (ref "STM32") (pin "4") (pinfunction "PC15/OSC32_OUT_4") (pintype "bidirectional"))
    )
    (net (code "83") (name "unconnected-(STM32A-PD2-Pad54)") (class "Default")
      (node (ref "STM32") (pin "54") (pinfunction "PD2_54") (pintype "bidirectional"))
    )
    (net (code "84") (name "unconnected-(VREG_5-VOUT_1-Pad2)") (class "Default")
      (node (ref "VREG_5") (pin "2") (pinfunction "VOUT_1_2") (pintype "bidirectional"))
    )
    (net (code "85") (name "unconnected-(VREG_33-VOUT_1-Pad2)") (class "Default")
      (node (ref "VREG_33") (pin "2") (pinfunction "VOUT_1_2") (pintype "output"))
    )
  )
)
